# USB-RS485_ConversionAdapter_ver2_1.net
KiCad netlist of a schematic drawn in EAGLE
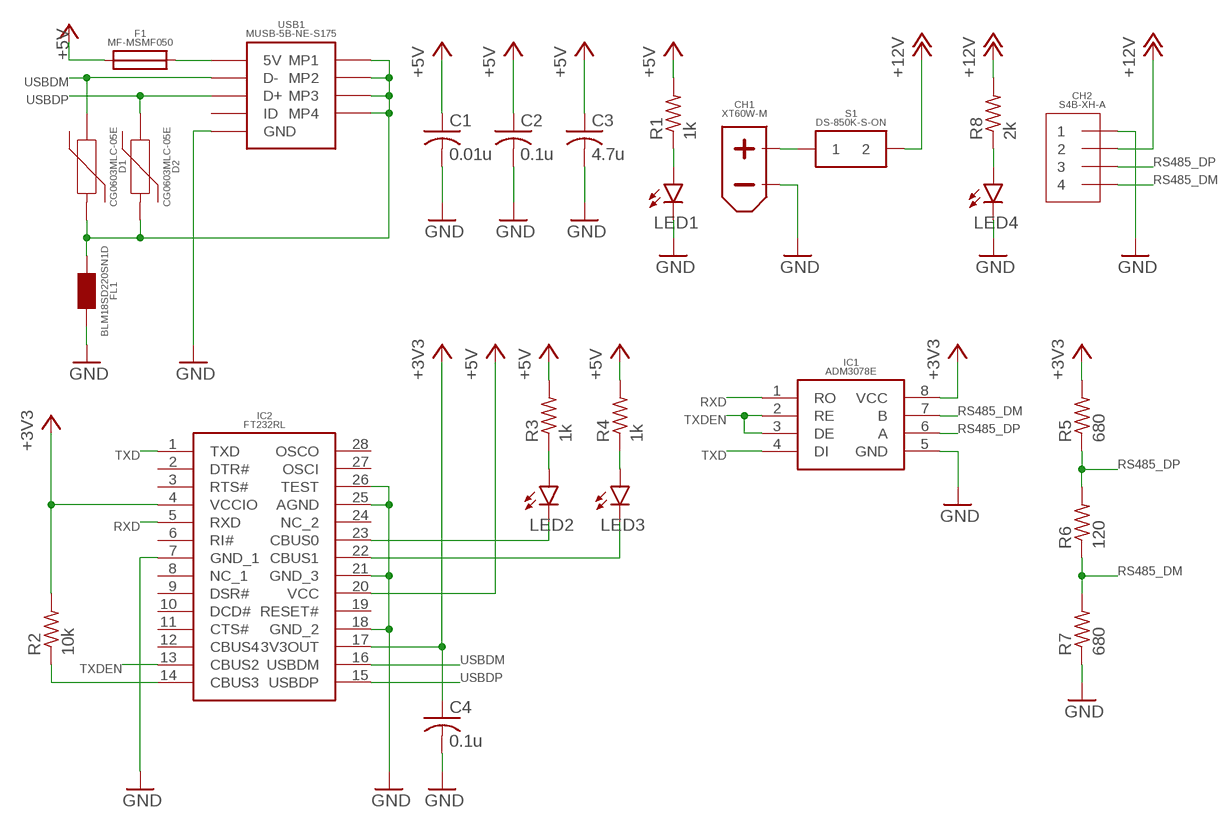
[diagram p0: schematic, sheet 1]

(export (version "E")
  (design (tool "Eeschema 10.0.6"))
  (components
    (comp (ref "C1")
      (value "0.01u")
      (footprint "eagle-import:C0603")
      (libsource (lib "eagle-import") (part "C-USC0603"))
    )
    (comp (ref "C2")
      (value "0.1u")
      (footprint "eagle-import:C0603")
      (libsource (lib "eagle-import") (part "C-USC0603"))
    )
    (comp (ref "C3")
      (value "4.7u")
      (footprint "eagle-import:C0603")
      (libsource (lib "eagle-import") (part "C-USC0603"))
    )
    (comp (ref "C4")
      (value "0.1u")
      (footprint "eagle-import:C0603")
      (libsource (lib "eagle-import") (part "C-USC0603"))
    )
    (comp (ref "CH1")
      (value "XT60PW-M")
      (footprint "eagle-import:XT60PW-M")
      (libsource (lib "eagle-import") (part "XT60PW-M"))
    )
    (comp (ref "CH2")
      (value "S4B-XH-A")
      (footprint "eagle-import:S4B-XH-A")
      (libsource (lib "eagle-import") (part "S4B-XH-A"))
    )
    (comp (ref "D1")
      (value "CG0603MLC-05E")
      (footprint "eagle-import:CG0603MLC-05E")
      (libsource (lib "eagle-import") (part "CG0603MLC-05E"))
    )
    (comp (ref "D2")
      (value "CG0603MLC-05E")
      (footprint "eagle-import:CG0603MLC-05E")
      (libsource (lib "eagle-import") (part "CG0603MLC-05E"))
    )
    (comp (ref "F1")
      (value "MF-MSMF050")
      (footprint "eagle-import:MF-MSMF050")
      (libsource (lib "eagle-import") (part "MF-MSMF050"))
    )
    (comp (ref "FL1")
      (value "BLM18SD220SN1D")
      (footprint "eagle-import:BLM18SD220SN1D")
      (libsource (lib "eagle-import") (part "BLM18SD220SN1D"))
    )
    (comp (ref "IC1")
      (value "ADM3078E")
      (footprint "eagle-import:ADM3078E")
      (libsource (lib "eagle-import") (part "ADM3078E"))
    )
    (comp (ref "IC2")
      (value "FT232RL")
      (footprint "eagle-import:FT232RL")
      (libsource (lib "eagle-import") (part "FT232RL"))
    )
    (comp (ref "LED1")
      (value "LEDSML0603")
      (footprint "eagle-import:SML0603")
      (libsource (lib "eagle-import") (part "LEDSML0603"))
    )
    (comp (ref "LED2")
      (value "LEDSML0603")
      (footprint "eagle-import:SML0603")
      (libsource (lib "eagle-import") (part "LEDSML0603"))
    )
    (comp (ref "LED3")
      (value "LEDSML0603")
      (footprint "eagle-import:SML0603")
      (libsource (lib "eagle-import") (part "LEDSML0603"))
    )
    (comp (ref "LED4")
      (value "LEDSML0603")
      (footprint "eagle-import:SML0603")
      (libsource (lib "eagle-import") (part "LEDSML0603"))
    )
    (comp (ref "R1")
      (value "1k")
      (footprint "eagle-import:R0603")
      (libsource (lib "eagle-import") (part "R-US_R0603"))
    )
    (comp (ref "R2")
      (value "10k")
      (footprint "eagle-import:R0603")
      (libsource (lib "eagle-import") (part "R-US_R0603"))
    )
    (comp (ref "R3")
      (value "1k")
      (footprint "eagle-import:R0603")
      (libsource (lib "eagle-import") (part "R-US_R0603"))
    )
    (comp (ref "R4")
      (value "1k")
      (footprint "eagle-import:R0603")
      (libsource (lib "eagle-import") (part "R-US_R0603"))
    )
    (comp (ref "R5")
      (value "680")
      (footprint "eagle-import:R0603")
      (libsource (lib "eagle-import") (part "R-US_R0603"))
    )
    (comp (ref "R6")
      (value "120")
      (footprint "eagle-import:R0603")
      (libsource (lib "eagle-import") (part "R-US_R0603"))
    )
    (comp (ref "R7")
      (value "680")
      (footprint "eagle-import:R0603")
      (libsource (lib "eagle-import") (part "R-US_R0603"))
    )
    (comp (ref "R8")
      (value "2k")
      (footprint "eagle-import:R0603")
      (libsource (lib "eagle-import") (part "R-US_R0603"))
    )
    (comp (ref "S1")
      (value "DS-850K-S-ON")
      (footprint "eagle-import:DS-850K-S-ON")
      (libsource (lib "eagle-import") (part "DS-850K-S-ON"))
    )
    (comp (ref "USB1")
      (value "MINI_USB_B_SMD")
      (footprint "eagle-import:MINI_USB_B_SMD")
      (libsource (lib "eagle-import") (part "MINI_USB_B_SMD"))
    )
  )
  (nets
    (net (code "1") (name "+3V3") (class "Default")
      (node (ref "C4") (pin "1") (pinfunction "1_1") (pintype "passive"))
      (node (ref "IC1") (pin "8") (pinfunction "VCC_8") (pintype "bidirectional"))
      (node (ref "IC2") (pin "17") (pinfunction "3V3OUT_17") (pintype "bidirectional"))
      (node (ref "IC2") (pin "4") (pinfunction "VCCIO_4") (pintype "bidirectional"))
      (node (ref "R2") (pin "2") (pinfunction "2_2") (pintype "passive"))
      (node (ref "R5") (pin "2") (pinfunction "2_2") (pintype "passive"))
    )
    (net (code "2") (name "+5V") (class "Default")
      (node (ref "C1") (pin "1") (pinfunction "1_1") (pintype "passive"))
      (node (ref "C2") (pin "1") (pinfunction "1_1") (pintype "passive"))
      (node (ref "C3") (pin "1") (pinfunction "1_1") (pintype "passive"))
      (node (ref "F1") (pin "1") (pinfunction "1_1") (pintype "bidirectional"))
      (node (ref "IC2") (pin "20") (pinfunction "VCC_20") (pintype "bidirectional"))
      (node (ref "R1") (pin "2") (pinfunction "2_2") (pintype "passive"))
      (node (ref "R3") (pin "2") (pinfunction "2_2") (pintype "passive"))
      (node (ref "R4") (pin "2") (pinfunction "2_2") (pintype "passive"))
    )
    (net (code "3") (name "+12V") (class "Default")
      (node (ref "CH2") (pin "2") (pinfunction "2_2") (pintype "bidirectional"))
      (node (ref "R8") (pin "2") (pinfunction "2_2") (pintype "passive"))
      (node (ref "S1") (pin "2B") (pinfunction "2_2B") (pintype "bidirectional"))
      (node (ref "S1") (pin "2T") (pinfunction "2_2T") (pintype "bidirectional"))
    )
    (net (code "4") (name "/RS485_DM") (class "Default")
      (node (ref "CH2") (pin "4") (pinfunction "4_4") (pintype "bidirectional"))
      (node (ref "IC1") (pin "7") (pinfunction "B_7") (pintype "bidirectional"))
      (node (ref "R6") (pin "1") (pinfunction "1_1") (pintype "passive"))
      (node (ref "R7") (pin "2") (pinfunction "2_2") (pintype "passive"))
    )
    (net (code "5") (name "/RS485_DP") (class "Default")
      (node (ref "CH2") (pin "3") (pinfunction "3_3") (pintype "bidirectional"))
      (node (ref "IC1") (pin "6") (pinfunction "A_6") (pintype "bidirectional"))
      (node (ref "R5") (pin "1") (pinfunction "1_1") (pintype "passive"))
      (node (ref "R6") (pin "2") (pinfunction "2_2") (pintype "passive"))
    )
    (net (code "6") (name "/RXD") (class "Default")
      (node (ref "IC1") (pin "1") (pinfunction "RO_1") (pintype "bidirectional"))
      (node (ref "IC2") (pin "5") (pinfunction "RXD_5") (pintype "bidirectional"))
    )
    (net (code "7") (name "/TXD") (class "Default")
      (node (ref "IC1") (pin "4") (pinfunction "DI_4") (pintype "bidirectional"))
      (node (ref "IC2") (pin "1") (pinfunction "TXD_1") (pintype "bidirectional"))
    )
    (net (code "8") (name "/TXDEN") (class "Default")
      (node (ref "IC1") (pin "2") (pinfunction "RE_2") (pintype "bidirectional"))
      (node (ref "IC1") (pin "3") (pinfunction "DE_3") (pintype "bidirectional"))
      (node (ref "IC2") (pin "13") (pinfunction "CBUS2_13") (pintype "bidirectional"))
    )
    (net (code "9") (name "/USBDM") (class "Default")
      (node (ref "D1") (pin "1") (pinfunction "1_1") (pintype "bidirectional"))
      (node (ref "IC2") (pin "16") (pinfunction "USBDM_16") (pintype "bidirectional"))
      (node (ref "USB1") (pin "2") (pinfunction "D-_2") (pintype "bidirectional"))
    )
    (net (code "10") (name "/USBDP") (class "Default")
      (node (ref "D2") (pin "1") (pinfunction "1_1") (pintype "bidirectional"))
      (node (ref "IC2") (pin "15") (pinfunction "USBDP_15") (pintype "bidirectional"))
      (node (ref "USB1") (pin "3") (pinfunction "D+_3") (pintype "bidirectional"))
    )
    (net (code "11") (name "GND") (class "Default")
      (node (ref "C1") (pin "2") (pinfunction "2_2") (pintype "passive"))
      (node (ref "C2") (pin "2") (pinfunction "2_2") (pintype "passive"))
      (node (ref "C3") (pin "2") (pinfunction "2_2") (pintype "passive"))
      (node (ref "C4") (pin "2") (pinfunction "2_2") (pintype "passive"))
      (node (ref "CH1") (pin "-") (pinfunction "-_-") (pintype "power_in"))
      (node (ref "CH2") (pin "1") (pinfunction "1_1") (pintype "bidirectional"))
      (node (ref "FL1") (pin "2") (pinfunction "2_2") (pintype "bidirectional"))
      (node (ref "IC1") (pin "5") (pinfunction "GND_5") (pintype "bidirectional"))
      (node (ref "IC2") (pin "18") (pinfunction "GND_2_18") (pintype "bidirectional"))
      (node (ref "IC2") (pin "21") (pinfunction "GND_3_21") (pintype "bidirectional"))
      (node (ref "IC2") (pin "25") (pinfunction "AGND_25") (pintype "bidirectional"))
      (node (ref "IC2") (pin "26") (pinfunction "TEST_26") (pintype "bidirectional"))
      (node (ref "IC2") (pin "7") (pinfunction "GND_1_7") (pintype "bidirectional"))
      (node (ref "LED1") (pin "C") (pinfunction "C_C") (pintype "passive"))
      (node (ref "LED4") (pin "C") (pinfunction "C_C") (pintype "passive"))
      (node (ref "R7") (pin "1") (pinfunction "1_1") (pintype "passive"))
      (node (ref "USB1") (pin "5") (pinfunction "GND_5") (pintype "bidirectional"))
    )
    (net (code "12") (name "Net-(CH1-Pad+)") (class "Default")
      (node (ref "CH1") (pin "+") (pinfunction "+_+") (pintype "power_in"))
      (node (ref "S1") (pin "1B") (pinfunction "1_1B") (pintype "bidirectional"))
      (node (ref "S1") (pin "1T") (pinfunction "1_1T") (pintype "bidirectional"))
    )
    (net (code "13") (name "Net-(D1-Pad2)") (class "Default")
      (node (ref "D1") (pin "2") (pinfunction "2_2") (pintype "bidirectional"))
      (node (ref "D2") (pin "2") (pinfunction "2_2") (pintype "bidirectional"))
      (node (ref "FL1") (pin "1") (pinfunction "1_1") (pintype "bidirectional"))
      (node (ref "USB1") (pin "MP1") (pinfunction "MP1_MP1") (pintype "bidirectional"))
      (node (ref "USB1") (pin "MP2") (pinfunction "MP2_MP2") (pintype "bidirectional"))
      (node (ref "USB1") (pin "MP3") (pinfunction "MP3_MP3") (pintype "bidirectional"))
      (node (ref "USB1") (pin "MP4") (pinfunction "MP4_MP4") (pintype "bidirectional"))
    )
    (net (code "14") (name "Net-(IC2-CBUS0)") (class "Default")
      (node (ref "IC2") (pin "23") (pinfunction "CBUS0_23") (pintype "bidirectional"))
      (node (ref "LED2") (pin "C") (pinfunction "C_C") (pintype "passive"))
    )
    (net (code "15") (name "Net-(IC2-CBUS1)") (class "Default")
      (node (ref "IC2") (pin "22") (pinfunction "CBUS1_22") (pintype "bidirectional"))
      (node (ref "LED3") (pin "C") (pinfunction "C_C") (pintype "passive"))
    )
    (net (code "16") (name "Net-(IC2-CBUS3)") (class "Default")
      (node (ref "IC2") (pin "14") (pinfunction "CBUS3_14") (pintype "bidirectional"))
      (node (ref "R2") (pin "1") (pinfunction "1_1") (pintype "passive"))
    )
    (net (code "17") (name "Net-(LED1-PadA)") (class "Default")
      (node (ref "LED1") (pin "A") (pinfunction "A_A") (pintype "passive"))
      (node (ref "R1") (pin "1") (pinfunction "1_1") (pintype "passive"))
    )
    (net (code "18") (name "Net-(LED2-PadA)") (class "Default")
      (node (ref "LED2") (pin "A") (pinfunction "A_A") (pintype "passive"))
      (node (ref "R3") (pin "1") (pinfunction "1_1") (pintype "passive"))
    )
    (net (code "19") (name "Net-(LED3-PadA)") (class "Default")
      (node (ref "LED3") (pin "A") (pinfunction "A_A") (pintype "passive"))
      (node (ref "R4") (pin "1") (pinfunction "1_1") (pintype "passive"))
    )
    (net (code "20") (name "Net-(LED4-PadA)") (class "Default")
      (node (ref "LED4") (pin "A") (pinfunction "A_A") (pintype "passive"))
      (node (ref "R8") (pin "1") (pinfunction "1_1") (pintype "passive"))
    )
    (net (code "21") (name "Net-(USB1-5V)") (class "Default")
      (node (ref "F1") (pin "2") (pinfunction "2_2") (pintype "bidirectional"))
      (node (ref "USB1") (pin "1") (pinfunction "5V_1") (pintype "bidirectional"))
    )
    (net (code "22") (name "unconnected-(IC2-CBUS4-Pad12)") (class "Default")
      (node (ref "IC2") (pin "12") (pinfunction "CBUS4_12") (pintype "bidirectional"))
    )
    (net (code "23") (name "unconnected-(IC2-CTS#-Pad11)") (class "Default")
      (node (ref "IC2") (pin "11") (pinfunction "CTS#_11") (pintype "bidirectional"))
    )
    (net (code "24") (name "unconnected-(IC2-DCD#-Pad10)") (class "Default")
      (node (ref "IC2") (pin "10") (pinfunction "DCD#_10") (pintype "bidirectional"))
    )
    (net (code "25") (name "unconnected-(IC2-DSR#-Pad9)") (class "Default")
      (node (ref "IC2") (pin "9") (pinfunction "DSR#_9") (pintype "bidirectional"))
    )
    (net (code "26") (name "unconnected-(IC2-DTR#-Pad2)") (class "Default")
      (node (ref "IC2") (pin "2") (pinfunction "DTR#_2") (pintype "bidirectional"))
    )
    (net (code "27") (name "unconnected-(IC2-NC_1-Pad8)") (class "Default")
      (node (ref "IC2") (pin "8") (pinfunction "NC_1_8") (pintype "bidirectional"))
    )
    (net (code "28") (name "unconnected-(IC2-NC_2-Pad24)") (class "Default")
      (node (ref "IC2") (pin "24") (pinfunction "NC_2_24") (pintype "bidirectional"))
    )
    (net (code "29") (name "unconnected-(IC2-OSCI-Pad27)") (class "Default")
      (node (ref "IC2") (pin "27") (pinfunction "OSCI_27") (pintype "bidirectional"))
    )
    (net (code "30") (name "unconnected-(IC2-OSCO-Pad28)") (class "Default")
      (node (ref "IC2") (pin "28") (pinfunction "OSCO_28") (pintype "bidirectional"))
    )
    (net (code "31") (name "unconnected-(IC2-RESET#-Pad19)") (class "Default")
      (node (ref "IC2") (pin "19") (pinfunction "RESET#_19") (pintype "bidirectional"))
    )
    (net (code "32") (name "unconnected-(IC2-RI#-Pad6)") (class "Default")
      (node (ref "IC2") (pin "6") (pinfunction "RI#_6") (pintype "bidirectional"))
    )
    (net (code "33") (name "unconnected-(IC2-RTS#-Pad3)") (class "Default")
      (node (ref "IC2") (pin "3") (pinfunction "RTS#_3") (pintype "bidirectional"))
    )
    (net (code "34") (name "unconnected-(USB1-ID-Pad4)") (class "Default")
      (node (ref "USB1") (pin "4") (pinfunction "ID_4") (pintype "bidirectional"))
    )
  )
)
